# smoothieboard-5driver_0.net
KiCad netlist of a schematic drawn in Altium Designer
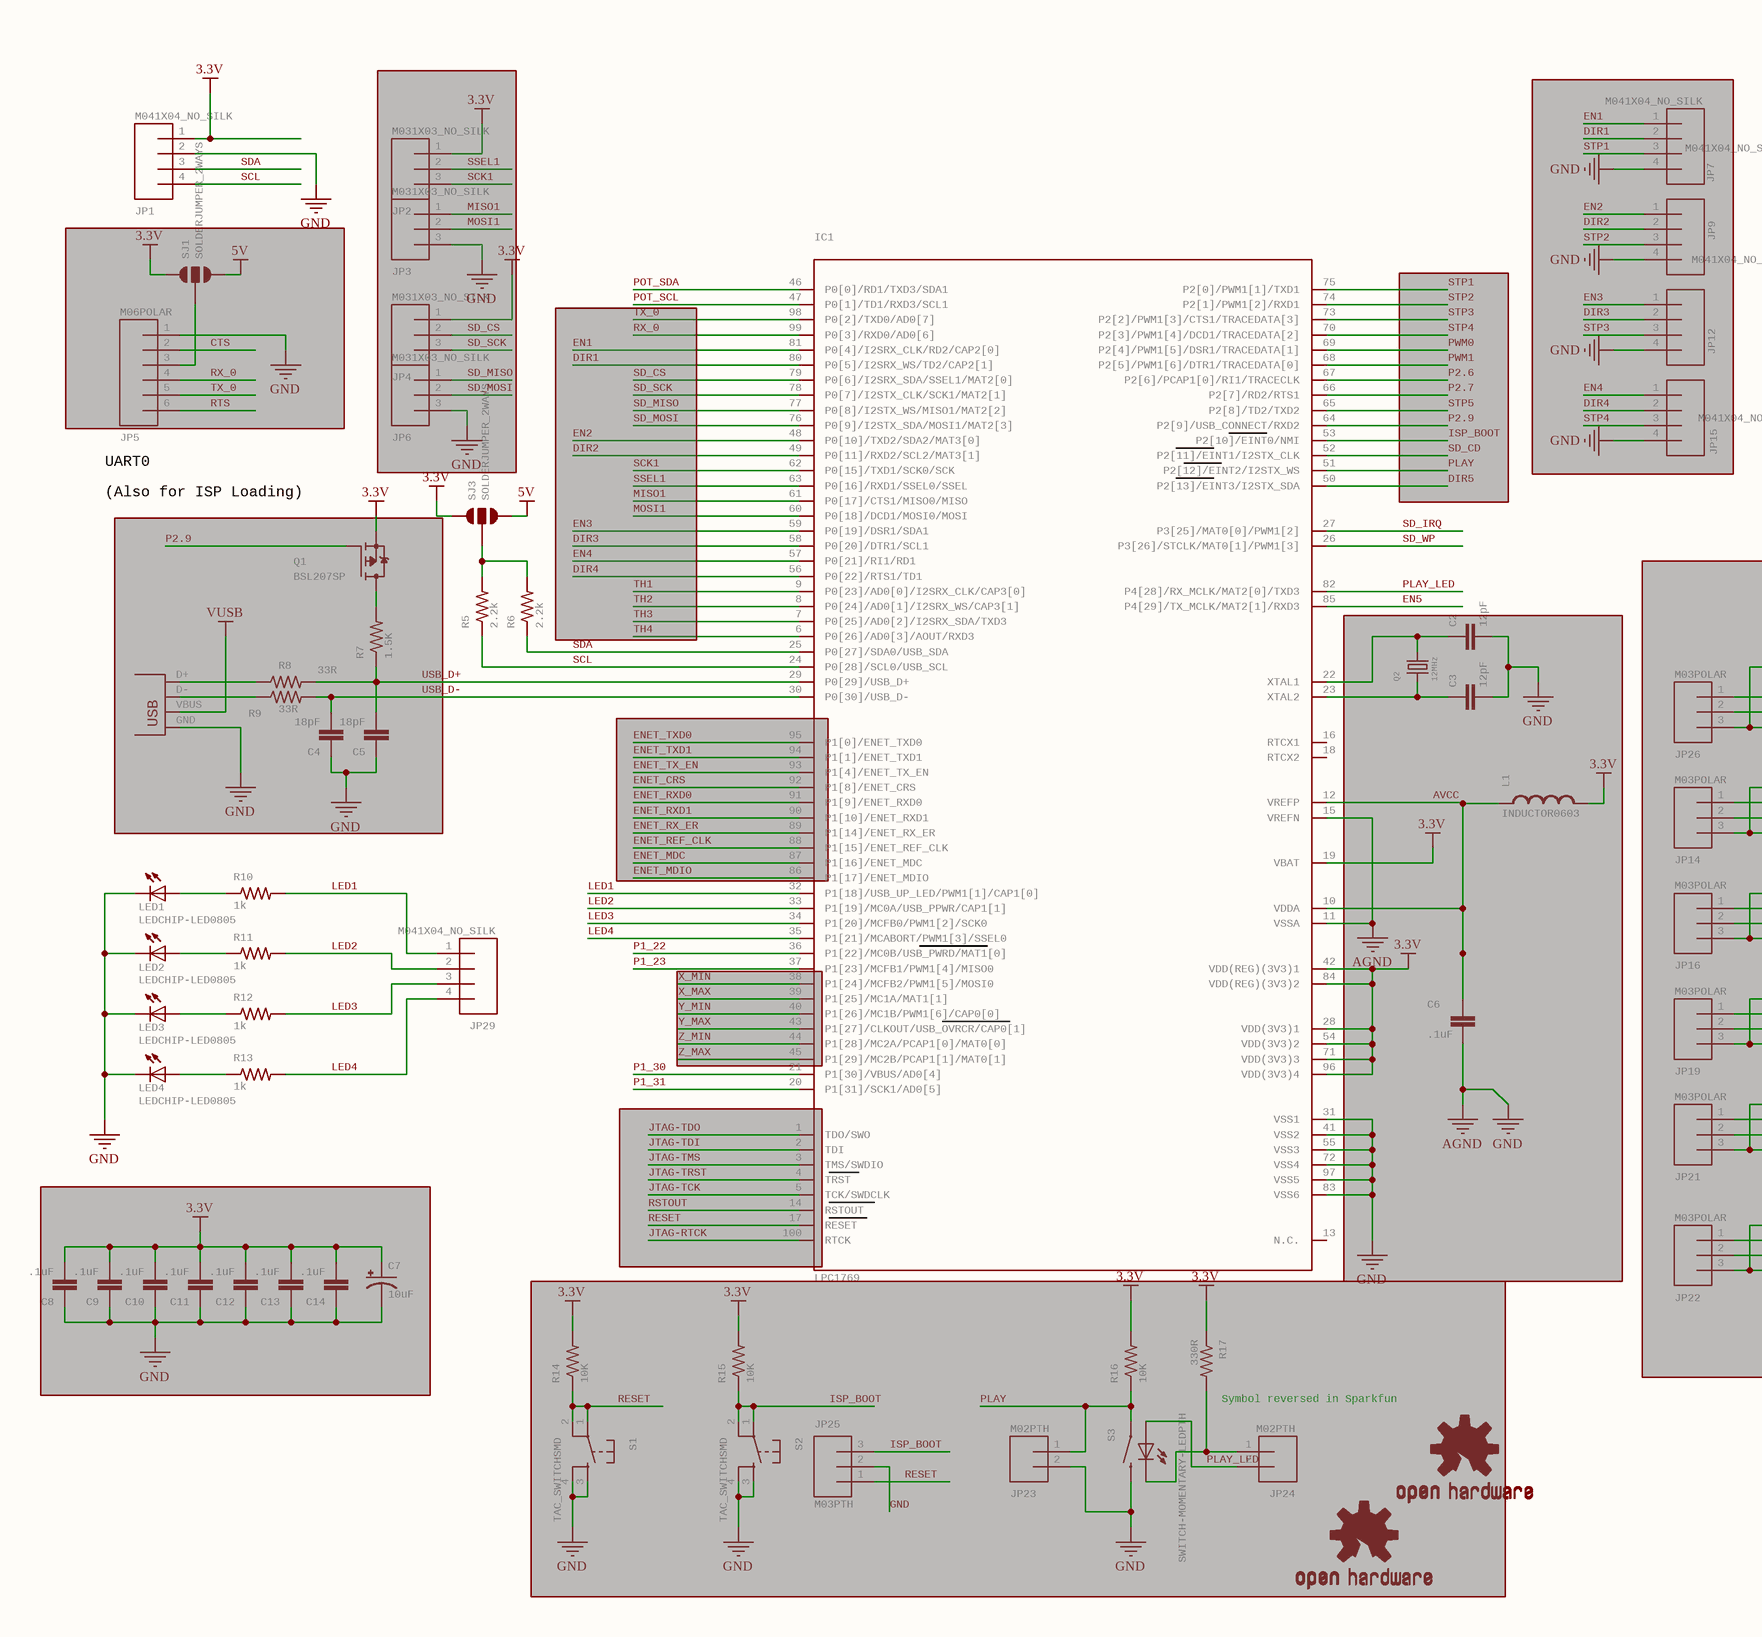
[diagram p0: smoothieboard-5driver_0.SchDoc, left]
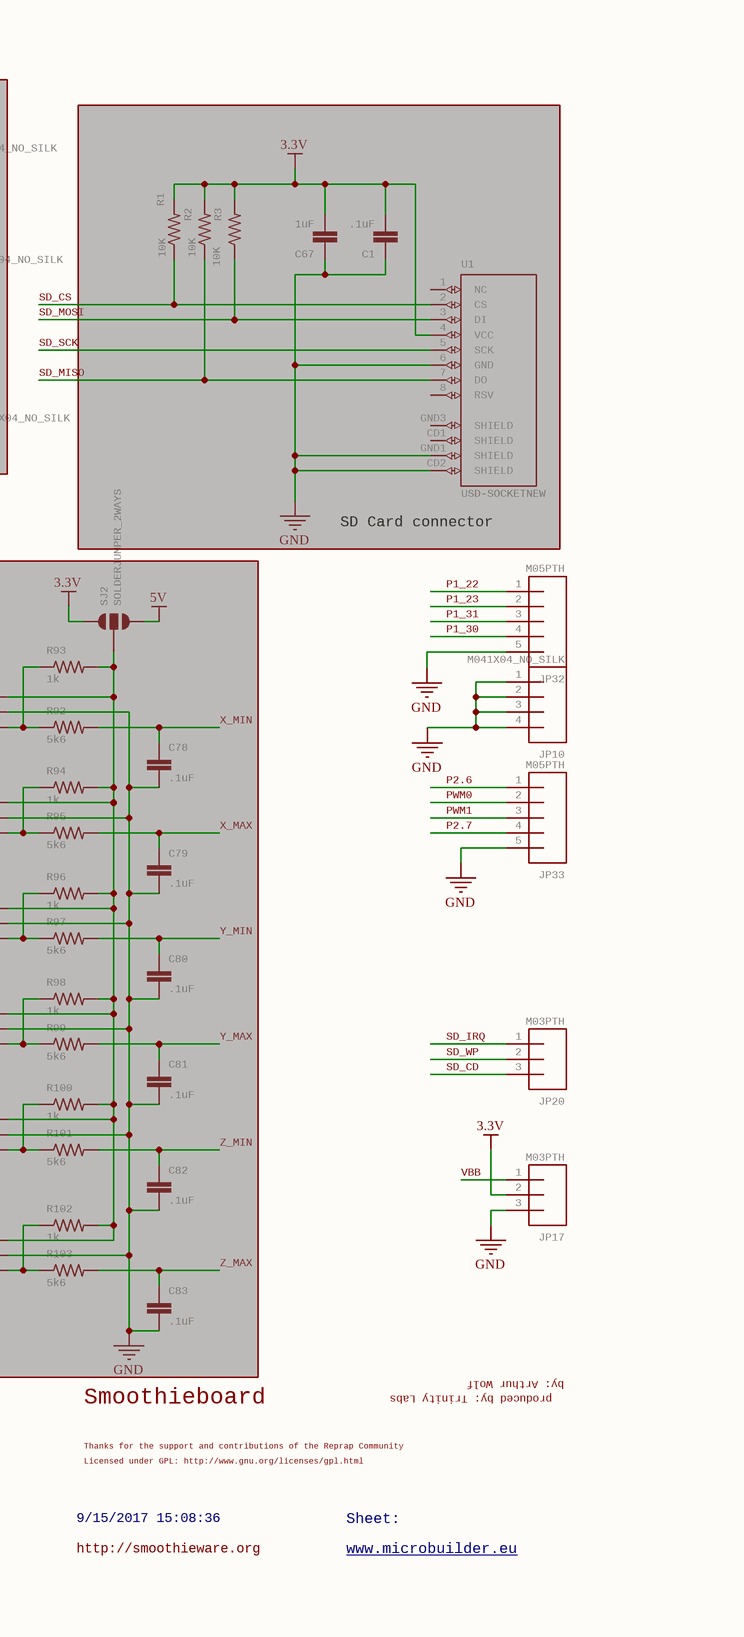
[diagram p1: smoothieboard-5driver_0.SchDoc, right]

(export (version "E")
  (design (tool "Eeschema 10.0.6"))
  (components
    (comp (ref "C1")
      (value ".1uF")
      (footprint "C0603")
      (description "CAPACITOR, European symbol")
      (libsource (lib "resistor") (part "C-EUC0603"))
    )
    (comp (ref "C2")
      (value "12pF")
      (footprint "C0603")
      (description "CAPACITOR, European symbol")
      (libsource (lib "") (part "C-EUC0603_2"))
    )
    (comp (ref "C3")
      (value "12pF")
      (footprint "C0603")
      (description "CAPACITOR, European symbol")
      (libsource (lib "") (part "C-EUC0603_2"))
    )
    (comp (ref "C4")
      (value "18pF")
      (footprint "C0603")
      (description "CAPACITOR, European symbol")
      (libsource (lib "rcl") (part "C-EUC0603"))
    )
    (comp (ref "C5")
      (value "18pF")
      (footprint "C0603")
      (description "CAPACITOR, European symbol")
      (libsource (lib "rcl") (part "C-EUC0603"))
    )
    (comp (ref "C6")
      (value ".1uF")
      (footprint "C0603")
      (description "CAPACITOR, European symbol")
      (libsource (lib "") (part "C-EUC0603_1"))
    )
    (comp (ref "C7") (value "10uF") (footprint "EIA3216") (libsource (lib "SparkFun") (part "CAP_POL1206")))
    (comp (ref "C8")
      (value ".1uF")
      (footprint "C0603")
      (description "CAPACITOR, European symbol")
      (libsource (lib "rcl") (part "C-EUC0603"))
    )
    (comp (ref "C9")
      (value ".1uF")
      (footprint "C0603")
      (description "CAPACITOR, European symbol")
      (libsource (lib "rcl") (part "C-EUC0603"))
    )
    (comp (ref "C10")
      (value ".1uF")
      (footprint "C0603")
      (description "CAPACITOR, European symbol")
      (libsource (lib "rcl") (part "C-EUC0603"))
    )
    (comp (ref "C11")
      (value ".1uF")
      (footprint "C0603")
      (description "CAPACITOR, European symbol")
      (libsource (lib "rcl") (part "C-EUC0603"))
    )
    (comp (ref "C12")
      (value ".1uF")
      (footprint "C0603")
      (description "CAPACITOR, European symbol")
      (libsource (lib "rcl") (part "C-EUC0603"))
    )
    (comp (ref "C13")
      (value ".1uF")
      (footprint "C0603")
      (description "CAPACITOR, European symbol")
      (libsource (lib "rcl") (part "C-EUC0603"))
    )
    (comp (ref "C14")
      (value ".1uF")
      (footprint "C0603")
      (description "CAPACITOR, European symbol")
      (libsource (lib "rcl") (part "C-EUC0603"))
    )
    (comp (ref "C67")
      (value "1uF")
      (footprint "C0805")
      (description "CAPACITOR, European symbol")
      (libsource (lib "resistor") (part "C-EUC0805"))
    )
    (comp (ref "C78")
      (value ".1uF")
      (footprint "C0603")
      (description "CAPACITOR, European symbol")
      (libsource (lib "") (part "C-EUC0603_1"))
    )
    (comp (ref "C79")
      (value ".1uF")
      (footprint "C0603")
      (description "CAPACITOR, European symbol")
      (libsource (lib "") (part "C-EUC0603_1"))
    )
    (comp (ref "C80")
      (value ".1uF")
      (footprint "C0603")
      (description "CAPACITOR, European symbol")
      (libsource (lib "") (part "C-EUC0603_1"))
    )
    (comp (ref "C81")
      (value ".1uF")
      (footprint "C0603")
      (description "CAPACITOR, European symbol")
      (libsource (lib "") (part "C-EUC0603_1"))
    )
    (comp (ref "C82")
      (value ".1uF")
      (footprint "C0603")
      (description "CAPACITOR, European symbol")
      (libsource (lib "") (part "C-EUC0603_1"))
    )
    (comp (ref "C83")
      (value ".1uF")
      (footprint "C0603")
      (description "CAPACITOR, European symbol")
      (libsource (lib "") (part "C-EUC0603_1"))
    )
    (comp (ref "IC1")
      (value "LPC1769")
      (footprint "LQFP100")
      (libsource (lib "microbuilder") (part "LPC1768"))
    )
    (comp (ref "JP1")
      (value "M041X04_NO_SILK")
      (footprint "1X04_NO_SILK")
      (libsource (lib "SparkFun") (part "M041X04_NO_SILK"))
    )
    (comp (ref "JP2")
      (value "M031X03_NO_SILK")
      (footprint "1X03_NO_SILK")
      (libsource (lib "SparkFun") (part "M031X03_NO_SILK"))
    )
    (comp (ref "JP3")
      (value "M031X03_NO_SILK")
      (footprint "1X03_NO_SILK")
      (libsource (lib "SparkFun") (part "M031X03_NO_SILK"))
    )
    (comp (ref "JP4")
      (value "M031X03_NO_SILK")
      (footprint "1X03_NO_SILK")
      (libsource (lib "SparkFun") (part "M031X03_NO_SILK"))
    )
    (comp (ref "JP5")
      (value "M06POLAR")
      (footprint "MOLEX-1X6")
      (libsource (lib "SparkFun") (part "M06POLAR"))
    )
    (comp (ref "JP6")
      (value "M031X03_NO_SILK")
      (footprint "1X03_NO_SILK")
      (libsource (lib "SparkFun") (part "M031X03_NO_SILK"))
    )
    (comp (ref "JP7")
      (value "M041X04_NO_SILK")
      (footprint "1X04_NO_SILK")
      (libsource (lib "SparkFun") (part "M041X04_NO_SILK"))
    )
    (comp (ref "JP9")
      (value "M041X04_NO_SILK")
      (footprint "1X04_NO_SILK")
      (libsource (lib "SparkFun") (part "M041X04_NO_SILK"))
    )
    (comp (ref "JP10")
      (value "M041X04_NO_SILK")
      (footprint "1X04_NO_SILK")
      (libsource (lib "SparkFun") (part "M041X04_NO_SILK"))
    )
    (comp (ref "JP12")
      (value "M041X04_NO_SILK")
      (footprint "1X04_NO_SILK")
      (libsource (lib "SparkFun") (part "M041X04_NO_SILK"))
    )
    (comp (ref "JP14")
      (value "M03POLAR")
      (footprint "MOLEX-1X3")
      (libsource (lib "SparkFun") (part "M03POLAR"))
    )
    (comp (ref "JP15")
      (value "M041X04_NO_SILK")
      (footprint "1X04_NO_SILK")
      (libsource (lib "SparkFun") (part "M041X04_NO_SILK"))
    )
    (comp (ref "JP16")
      (value "M03POLAR")
      (footprint "MOLEX-1X3")
      (libsource (lib "SparkFun") (part "M03POLAR"))
    )
    (comp (ref "JP17") (value "M03PTH") (footprint "1X03") (libsource (lib "SparkFun") (part "M03PTH")))
    (comp (ref "JP19")
      (value "M03POLAR")
      (footprint "MOLEX-1X3")
      (libsource (lib "SparkFun") (part "M03POLAR"))
    )
    (comp (ref "JP20") (value "M03PTH") (footprint "1X03") (libsource (lib "SparkFun") (part "M03PTH")))
    (comp (ref "JP21")
      (value "M03POLAR")
      (footprint "MOLEX-1X3")
      (libsource (lib "SparkFun") (part "M03POLAR"))
    )
    (comp (ref "JP22")
      (value "M03POLAR")
      (footprint "MOLEX-1X3")
      (libsource (lib "SparkFun") (part "M03POLAR"))
    )
    (comp (ref "JP23") (value "M02PTH") (footprint "1X02") (libsource (lib "SparkFun") (part "M02PTH")))
    (comp (ref "JP24") (value "M02PTH") (footprint "1X02") (libsource (lib "SparkFun") (part "M02PTH")))
    (comp (ref "JP25")
      (value "M03PTH")
      (footprint "1X03")
      (libsource (lib "SparkFun-Connectors") (part "M03PTH"))
    )
    (comp (ref "JP26")
      (value "M03POLAR")
      (footprint "MOLEX-1X3")
      (libsource (lib "SparkFun") (part "M03POLAR"))
    )
    (comp (ref "JP29")
      (value "M041X04_NO_SILK")
      (footprint "1X04_NO_SILK")
      (libsource (lib "SparkFun") (part "M041X04_NO_SILK"))
    )
    (comp (ref "JP32") (value "M05PTH") (footprint "1X05") (libsource (lib "SparkFun") (part "M05PTH")))
    (comp (ref "JP33") (value "M05PTH") (footprint "1X05") (libsource (lib "SparkFun") (part "M05PTH")))
    (comp (ref "L1")
      (value "INDUCTOR0603")
      (footprint "0603")
      (libsource (lib "SparkFun") (part "INDUCTOR0603"))
    )
    (comp (ref "LED1")
      (value "LEDCHIP-LED0805")
      (footprint "CHIP-LED0805")
      (libsource (lib "led") (part "LEDCHIP-LED0805"))
    )
    (comp (ref "LED2")
      (value "LEDCHIP-LED0805")
      (footprint "CHIP-LED0805")
      (libsource (lib "led") (part "LEDCHIP-LED0805"))
    )
    (comp (ref "LED3")
      (value "LEDCHIP-LED0805")
      (footprint "CHIP-LED0805")
      (libsource (lib "led") (part "LEDCHIP-LED0805"))
    )
    (comp (ref "LED4")
      (value "LEDCHIP-LED0805")
      (footprint "CHIP-LED0805")
      (libsource (lib "led") (part "LEDCHIP-LED0805"))
    )
    (comp (ref "Q1")
      (value "BSL207SP")
      (footprint "SC74_INFINEON")
      (libsource (lib "transistor-fet") (part "BSL207SP"))
    )
    (comp (ref "Q2")
      (value "12MHz")
      (footprint "CRYSTAL_3.2X2.5")
      (libsource (lib "microbuilder") (part "CRYSTALTHIN"))
    )
    (comp (ref "R1")
      (value "10K")
      (footprint "R0603")
      (description "RESISTOR, American symbol")
      (libsource (lib "resistor") (part "R-US_R0603"))
    )
    (comp (ref "R2")
      (value "10K")
      (footprint "R0603")
      (description "RESISTOR, American symbol")
      (libsource (lib "resistor") (part "R-US_R0603"))
    )
    (comp (ref "R3")
      (value "10K")
      (footprint "R0603")
      (description "RESISTOR, American symbol")
      (libsource (lib "resistor") (part "R-US_R0603"))
    )
    (comp (ref "R5")
      (value "2.2k")
      (footprint "R0603")
      (description "RESISTOR, American symbol")
      (libsource (lib "resistor") (part "R-US_R0603"))
    )
    (comp (ref "R6")
      (value "2.2k")
      (footprint "R0603")
      (description "RESISTOR, American symbol")
      (libsource (lib "resistor") (part "R-US_R0603"))
    )
    (comp (ref "R7")
      (value "1.5K")
      (footprint "R0603")
      (description "RESISTOR, American symbol")
      (libsource (lib "resistor") (part "R-US_R0603"))
    )
    (comp (ref "R8")
      (value "33R")
      (footprint "R0603")
      (description "RESISTOR, American symbol")
      (libsource (lib "resistor") (part "R-US_R0603"))
    )
    (comp (ref "R9")
      (value "33R")
      (footprint "R0603")
      (description "RESISTOR, American symbol")
      (libsource (lib "resistor") (part "R-US_R0603"))
    )
    (comp (ref "R10")
      (value "1k")
      (footprint "R0603")
      (description "RESISTOR, American symbol")
      (libsource (lib "resistor") (part "R-US_R0603"))
    )
    (comp (ref "R11")
      (value "1k")
      (footprint "R0603")
      (description "RESISTOR, American symbol")
      (libsource (lib "resistor") (part "R-US_R0603"))
    )
    (comp (ref "R12")
      (value "1k")
      (footprint "R0603")
      (description "RESISTOR, American symbol")
      (libsource (lib "resistor") (part "R-US_R0603"))
    )
    (comp (ref "R13")
      (value "1k")
      (footprint "R0603")
      (description "RESISTOR, American symbol")
      (libsource (lib "resistor") (part "R-US_R0603"))
    )
    (comp (ref "R14")
      (value "10K")
      (footprint "R0603")
      (description "RESISTOR, American symbol")
      (libsource (lib "resistor") (part "R-US_R0603"))
    )
    (comp (ref "R15")
      (value "10K")
      (footprint "R0603")
      (description "RESISTOR, American symbol")
      (libsource (lib "resistor") (part "R-US_R0603"))
    )
    (comp (ref "R16")
      (value "10K")
      (footprint "R0603")
      (description "RESISTOR, American symbol")
      (libsource (lib "resistor") (part "R-US_R0603"))
    )
    (comp (ref "R17")
      (value "330R")
      (footprint "R0603")
      (description "RESISTOR, American symbol")
      (libsource (lib "resistor") (part "R-US_R0603"))
    )
    (comp (ref "R92")
      (value "5k6")
      (footprint "R0603")
      (description "RESISTOR, American symbol")
      (libsource (lib "resistor") (part "R-US_R0603"))
    )
    (comp (ref "R93")
      (value "1k")
      (footprint "R0603")
      (description "RESISTOR, American symbol")
      (libsource (lib "resistor") (part "R-US_R0603"))
    )
    (comp (ref "R94")
      (value "1k")
      (footprint "R0603")
      (description "RESISTOR, American symbol")
      (libsource (lib "resistor") (part "R-US_R0603"))
    )
    (comp (ref "R95")
      (value "5k6")
      (footprint "R0603")
      (description "RESISTOR, American symbol")
      (libsource (lib "resistor") (part "R-US_R0603"))
    )
    (comp (ref "R96")
      (value "1k")
      (footprint "R0603")
      (description "RESISTOR, American symbol")
      (libsource (lib "resistor") (part "R-US_R0603"))
    )
    (comp (ref "R97")
      (value "5k6")
      (footprint "R0603")
      (description "RESISTOR, American symbol")
      (libsource (lib "resistor") (part "R-US_R0603"))
    )
    (comp (ref "R98")
      (value "1k")
      (footprint "R0603")
      (description "RESISTOR, American symbol")
      (libsource (lib "resistor") (part "R-US_R0603"))
    )
    (comp (ref "R99")
      (value "5k6")
      (footprint "R0603")
      (description "RESISTOR, American symbol")
      (libsource (lib "resistor") (part "R-US_R0603"))
    )
    (comp (ref "R100")
      (value "1k")
      (footprint "R0603")
      (description "RESISTOR, American symbol")
      (libsource (lib "resistor") (part "R-US_R0603"))
    )
    (comp (ref "R101")
      (value "5k6")
      (footprint "R0603")
      (description "RESISTOR, American symbol")
      (libsource (lib "resistor") (part "R-US_R0603"))
    )
    (comp (ref "R102")
      (value "1k")
      (footprint "R0603")
      (description "RESISTOR, American symbol")
      (libsource (lib "resistor") (part "R-US_R0603"))
    )
    (comp (ref "R103")
      (value "5k6")
      (footprint "R0603")
      (description "RESISTOR, American symbol")
      (libsource (lib "resistor") (part "R-US_R0603"))
    )
    (comp (ref "S1")
      (value "TAC_SWITCHSMD")
      (footprint "TACTILE_SWITCH_SMD")
      (libsource (lib "SparkFun") (part "TAC_SWITCHSMD"))
    )
    (comp (ref "S2")
      (value "TAC_SWITCHSMD")
      (footprint "TACTILE_SWITCH_SMD")
      (libsource (lib "SparkFun") (part "TAC_SWITCHSMD"))
    )
    (comp (ref "S3")
      (value "SWITCH-MOMENTARY-LEDPTH")
      (footprint "TACTILE-PTH-LED-12MM")
      (libsource (lib "Local Library") (part "SWITCH-MOMENTARY-LEDPTH"))
    )
    (comp (ref "SJ1")
      (value "SOLDERJUMPER_2WAYS")
      (footprint "SJ_3")
      (description "Solder Jumper2 way solder jumper")
      (libsource (lib "SparkFun") (part "SOLDERJUMPER_2WAYS"))
    )
    (comp (ref "SJ2")
      (value "SOLDERJUMPER_2WAYS")
      (footprint "SJ_3")
      (description "Solder Jumper2 way solder jumper")
      (libsource (lib "SparkFun") (part "SOLDERJUMPER_2WAYS"))
    )
    (comp (ref "SJ3")
      (value "SOLDERJUMPER_2WAYS")
      (footprint "SJ_3")
      (description "Solder Jumper2 way solder jumper")
      (libsource (lib "SparkFun") (part "SOLDERJUMPER_2WAYS"))
    )
    (comp (ref "U$8")
      (value "OSHW-LOGOH")
      (footprint "OSHW-LOGO-HUGE")
      (fields (field (name "LIBRARYNAME") "logxen"))
      (libsource (lib "logxen") (part "OSHW-LOGOH"))
    )
    (comp (ref "U$9")
      (value "OSHW-LOGOH")
      (footprint "OSHW-LOGO-HUGE")
      (fields (field (name "LIBRARYNAME") "logxen"))
      (libsource (lib "logxen") (part "OSHW-LOGOH"))
    )
    (comp (ref "U1")
      (value "USD-SOCKETNEW")
      (footprint "MICRO-SD-SOCKET-PP")
      (libsource (lib "SparkFun") (part "USD-SOCKETNEW"))
    )
    (comp (ref "X14")
      (value "USBPTH")
      (footprint "USB-B-PTH")
      (fields (field (name "USB") "USB"))
      (libsource (lib "SparkFun") (part "USBPTH"))
    )
  )
  (nets
    (net (code "1") (name "/AVCC") (class "Default")
      (node (ref "C6") (pin "1") (pinfunction "1_1") (pintype "passive"))
      (node (ref "IC1") (pin "10") (pinfunction "VDDA_10") (pintype "bidirectional"))
      (node (ref "IC1") (pin "12") (pinfunction "VREFP_12") (pintype "bidirectional"))
      (node (ref "L1") (pin "1") (pinfunction "1_1") (pintype "passive"))
    )
    (net (code "2") (name "/CTS") (class "Default")
      (node (ref "JP5") (pin "2") (pinfunction "2_2") (pintype "passive"))
    )
    (net (code "3") (name "/DIR1") (class "Default")
      (node (ref "IC1") (pin "80") (pinfunction "P0[5]/I2SRX_WS/TD2/CAP2[1]_80") (pintype "bidirectional"))
      (node (ref "JP7") (pin "2") (pinfunction "2_2") (pintype "passive"))
    )
    (net (code "4") (name "/DIR2") (class "Default")
      (node (ref "IC1") (pin "49") (pinfunction "P0[11]/RXD2/SCL2/MAT3[1]_49") (pintype "bidirectional"))
      (node (ref "JP9") (pin "2") (pinfunction "2_2") (pintype "passive"))
    )
    (net (code "5") (name "/DIR3") (class "Default")
      (node (ref "IC1") (pin "58") (pinfunction "P0[20]/DTR1/SCL1_58") (pintype "bidirectional"))
      (node (ref "JP12") (pin "2") (pinfunction "2_2") (pintype "passive"))
    )
    (net (code "6") (name "/DIR4") (class "Default")
      (node (ref "IC1") (pin "56") (pinfunction "P0[22]/RTS1/TD1_56") (pintype "bidirectional"))
      (node (ref "JP15") (pin "2") (pinfunction "2_2") (pintype "passive"))
    )
    (net (code "7") (name "/DIR5") (class "Default")
      (node (ref "IC1") (pin "50") (pinfunction "P2[13]/EINT3/I2STX_SDA_50") (pintype "bidirectional"))
    )
    (net (code "8") (name "/EN1") (class "Default")
      (node (ref "IC1") (pin "81") (pinfunction "P0[4]/I2SRX_CLK/RD2/CAP2[0]_81") (pintype "bidirectional"))
      (node (ref "JP7") (pin "1") (pinfunction "1_1") (pintype "passive"))
    )
    (net (code "9") (name "/EN2") (class "Default")
      (node (ref "IC1") (pin "48") (pinfunction "P0[10]/TXD2/SDA2/MAT3[0]_48") (pintype "bidirectional"))
      (node (ref "JP9") (pin "1") (pinfunction "1_1") (pintype "passive"))
    )
    (net (code "10") (name "/EN3") (class "Default")
      (node (ref "IC1") (pin "59") (pinfunction "P0[19]/DSR1/SDA1_59") (pintype "bidirectional"))
      (node (ref "JP12") (pin "1") (pinfunction "1_1") (pintype "passive"))
    )
    (net (code "11") (name "/EN4") (class "Default")
      (node (ref "IC1") (pin "57") (pinfunction "P0[21]/RI1/RD1_57") (pintype "bidirectional"))
      (node (ref "JP15") (pin "1") (pinfunction "1_1") (pintype "passive"))
    )
    (net (code "12") (name "/EN5") (class "Default")
      (node (ref "IC1") (pin "85") (pinfunction "P4[29]/TX_MCLK/MAT2[1]/RXD3_85") (pintype "bidirectional"))
    )
    (net (code "13") (name "/ENET_CRS") (class "Default")
      (node (ref "IC1") (pin "92") (pinfunction "P1[8]/ENET_CRS_92") (pintype "bidirectional"))
    )
    (net (code "14") (name "/ENET_MDC") (class "Default")
      (node (ref "IC1") (pin "87") (pinfunction "P1[16]/ENET_MDC_87") (pintype "bidirectional"))
    )
    (net (code "15") (name "/ENET_MDIO") (class "Default")
      (node (ref "IC1") (pin "86") (pinfunction "P1[17]/ENET_MDIO_86") (pintype "bidirectional"))
    )
    (net (code "16") (name "/ENET_REF_CLK") (class "Default")
      (node (ref "IC1") (pin "88") (pinfunction "P1[15]/ENET_REF_CLK_88") (pintype "bidirectional"))
    )
    (net (code "17") (name "/ENET_RXD0") (class "Default")
      (node (ref "IC1") (pin "91") (pinfunction "P1[9]/ENET_RXD0_91") (pintype "bidirectional"))
    )
    (net (code "18") (name "/ENET_RXD1") (class "Default")
      (node (ref "IC1") (pin "90") (pinfunction "P1[10]/ENET_RXD1_90") (pintype "bidirectional"))
    )
    (net (code "19") (name "/ENET_RX_ER") (class "Default")
      (node (ref "IC1") (pin "89") (pinfunction "P1[14]/ENET_RX_ER_89") (pintype "bidirectional"))
    )
    (net (code "20") (name "/ENET_TXD0") (class "Default")
      (node (ref "IC1") (pin "95") (pinfunction "P1[0]/ENET_TXD0_95") (pintype "bidirectional"))
    )
    (net (code "21") (name "/ENET_TXD1") (class "Default")
      (node (ref "IC1") (pin "94") (pinfunction "P1[1]/ENET_TXD1_94") (pintype "bidirectional"))
    )
    (net (code "22") (name "/ENET_TX_EN") (class "Default")
      (node (ref "IC1") (pin "93") (pinfunction "P1[4]/ENET_TX_EN_93") (pintype "bidirectional"))
    )
    (net (code "23") (name "/ISP_BOOT") (class "Default")
      (node (ref "IC1") (pin "53") (pinfunction "P2[10]/EINT0/NMI_53") (pintype "bidirectional"))
      (node (ref "JP25") (pin "3") (pinfunction "3_3") (pintype "passive"))
      (node (ref "R15") (pin "1") (pinfunction "1_1") (pintype "passive"))
      (node (ref "S2") (pin "1") (pinfunction "1_1") (pintype "passive"))
      (node (ref "S2") (pin "2") (pinfunction "2_2") (pintype "passive"))
    )
    (net (code "24") (name "/JTAG-RTCK") (class "Default")
      (node (ref "IC1") (pin "100") (pinfunction "RTCK_100") (pintype "bidirectional"))
    )
    (net (code "25") (name "/JTAG-TCK") (class "Default")
      (node (ref "IC1") (pin "5") (pinfunction "TCK/SWDCLK_5") (pintype "bidirectional"))
    )
    (net (code "26") (name "/JTAG-TDI") (class "Default")
      (node (ref "IC1") (pin "2") (pinfunction "TDI_2") (pintype "bidirectional"))
    )
    (net (code "27") (name "/JTAG-TDO") (class "Default")
      (node (ref "IC1") (pin "1") (pinfunction "TDO/SWO_1") (pintype "bidirectional"))
    )
    (net (code "28") (name "/JTAG-TMS") (class "Default")
      (node (ref "IC1") (pin "3") (pinfunction "TMS/SWDIO_3") (pintype "bidirectional"))
    )
    (net (code "29") (name "/JTAG-TRST") (class "Default")
      (node (ref "IC1") (pin "4") (pinfunction "TRST_4") (pintype "bidirectional"))
    )
    (net (code "30") (name "/LED1") (class "Default")
      (node (ref "IC1") (pin "32") (pinfunction "P1[18]/USB_UP_LED/PWM1[1]/CAP1[0]_32") (pintype "bidirectional"))
      (node (ref "JP29") (pin "1") (pinfunction "1_1") (pintype "passive"))
      (node (ref "R10") (pin "2") (pinfunction "2_2") (pintype "passive"))
    )
    (net (code "31") (name "/LED2") (class "Default")
      (node (ref "IC1") (pin "33") (pinfunction "P1[19]/MC0A/USB_PPWR/CAP1[1]_33") (pintype "bidirectional"))
      (node (ref "JP29") (pin "2") (pinfunction "2_2") (pintype "passive"))
      (node (ref "R11") (pin "2") (pinfunction "2_2") (pintype "passive"))
    )
    (net (code "32") (name "/LED3") (class "Default")
      (node (ref "IC1") (pin "34") (pinfunction "P1[20]/MCFB0/PWM1[2]/SCK0_34") (pintype "bidirectional"))
      (node (ref "JP29") (pin "3") (pinfunction "3_3") (pintype "passive"))
      (node (ref "R12") (pin "2") (pinfunction "2_2") (pintype "passive"))
    )
    (net (code "33") (name "/LED4") (class "Default")
      (node (ref "IC1") (pin "35") (pinfunction "P1[21]/MCABORT/PWM1[3]/SSEL0_35") (pintype "bidirectional"))
      (node (ref "JP29") (pin "4") (pinfunction "4_4") (pintype "passive"))
      (node (ref "R13") (pin "2") (pinfunction "2_2") (pintype "passive"))
    )
    (net (code "34") (name "/MISO1") (class "Default")
      (node (ref "IC1") (pin "61") (pinfunction "P0[17]/CTS1/MISO0/MISO_61") (pintype "bidirectional"))
      (node (ref "JP3") (pin "1") (pinfunction "1_1") (pintype "passive"))
    )
    (net (code "35") (name "/MOSI1") (class "Default")
      (node (ref "IC1") (pin "60") (pinfunction "P0[18]/DCD1/MOSI0/MOSI_60") (pintype "bidirectional"))
      (node (ref "JP3") (pin "2") (pinfunction "2_2") (pintype "passive"))
    )
    (net (code "36") (name "/P1_22") (class "Default")
      (node (ref "IC1") (pin "36") (pinfunction "P1[22]/MC0B/USB_PWRD/MAT1[0]_36") (pintype "bidirectional"))
      (node (ref "JP32") (pin "1") (pinfunction "1_1") (pintype "passive"))
    )
    (net (code "37") (name "/P1_23") (class "Default")
      (node (ref "IC1") (pin "37") (pinfunction "P1[23]/MCFB1/PWM1[4]/MISO0_37") (pintype "bidirectional"))
      (node (ref "JP32") (pin "2") (pinfunction "2_2") (pintype "passive"))
    )
    (net (code "38") (name "/P1_30") (class "Default")
      (node (ref "IC1") (pin "21") (pinfunction "P1[30]/VBUS/AD0[4]_21") (pintype "bidirectional"))
      (node (ref "JP32") (pin "4") (pinfunction "4_4") (pintype "passive"))
    )
    (net (code "39") (name "/P1_31") (class "Default")
      (node (ref "IC1") (pin "20") (pinfunction "P1[31]/SCK1/AD0[5]_20") (pintype "bidirectional"))
      (node (ref "JP32") (pin "3") (pinfunction "3_3") (pintype "passive"))
    )
    (net (code "40") (name "/P2.6") (class "Default")
      (node (ref "IC1") (pin "67") (pinfunction "P2[6]/PCAP1[0]/RI1/TRACECLK_67") (pintype "bidirectional"))
      (node (ref "JP33") (pin "1") (pinfunction "1_1") (pintype "passive"))
    )
    (net (code "41") (name "/P2.7") (class "Default")
      (node (ref "IC1") (pin "66") (pinfunction "P2[7]/RD2/RTS1_66") (pintype "bidirectional"))
      (node (ref "JP33") (pin "4") (pinfunction "4_4") (pintype "passive"))
    )
    (net (code "42") (name "/P2.9") (class "Default")
      (node (ref "IC1") (pin "64") (pinfunction "P2[9]/USB_CONNECT/RXD2_64") (pintype "bidirectional"))
      (node (ref "Q1") (pin "3") (pinfunction "G_3") (pintype "passive"))
    )
    (net (code "43") (name "/PLAY") (class "Default")
      (node (ref "IC1") (pin "51") (pinfunction "P2[12]/EINT2/I2STX_WS_51") (pintype "bidirectional"))
      (node (ref "JP23") (pin "1") (pinfunction "1_1") (pintype "passive"))
      (node (ref "R16") (pin "1") (pinfunction "1_1") (pintype "passive"))
      (node (ref "S3") (pin "4") (pinfunction "1_4") (pintype "passive"))
    )
    (net (code "44") (name "/PLAY_LED") (class "Default")
      (node (ref "IC1") (pin "82") (pinfunction "P4[28]/RX_MCLK/MAT2[0]/TXD3_82") (pintype "bidirectional"))
      (node (ref "JP24") (pin "2") (pinfunction "2_2") (pintype "passive"))
      (node (ref "S3") (pin "A") (pinfunction "A_A") (pintype "passive"))
    )
    (net (code "45") (name "/POT_SCL") (class "Default")
      (node (ref "IC1") (pin "47") (pinfunction "P0[1]/TD1/RXD3/SCL1_47") (pintype "bidirectional"))
    )
    (net (code "46") (name "/POT_SDA") (class "Default")
      (node (ref "IC1") (pin "46") (pinfunction "P0[0]/RD1/TXD3/SDA1_46") (pintype "bidirectional"))
    )
    (net (code "47") (name "/PWM0") (class "Default")
      (node (ref "IC1") (pin "69") (pinfunction "P2[4]/PWM1[5]/DSR1/TRACEDATA[1]_69") (pintype "bidirectional"))
      (node (ref "JP33") (pin "2") (pinfunction "2_2") (pintype "passive"))
    )
    (net (code "48") (name "/PWM1") (class "Default")
      (node (ref "IC1") (pin "68") (pinfunction "P2[5]/PWM1[6]/DTR1/TRACEDATA[0]_68") (pintype "bidirectional"))
      (node (ref "JP33") (pin "3") (pinfunction "3_3") (pintype "passive"))
    )
    (net (code "49") (name "/RESET") (class "Default")
      (node (ref "IC1") (pin "17") (pinfunction "RESET_17") (pintype "bidirectional"))
      (node (ref "JP25") (pin "1") (pinfunction "1_1") (pintype "passive"))
      (node (ref "R14") (pin "1") (pinfunction "1_1") (pintype "passive"))
      (node (ref "S1") (pin "1") (pinfunction "1_1") (pintype "passive"))
      (node (ref "S1") (pin "2") (pinfunction "2_2") (pintype "passive"))
    )
    (net (code "50") (name "/RSTOUT") (class "Default")
      (node (ref "IC1") (pin "14") (pinfunction "RSTOUT_14") (pintype "bidirectional"))
    )
    (net (code "51") (name "/RTS") (class "Default")
      (node (ref "JP5") (pin "6") (pinfunction "6_6") (pintype "passive"))
    )
    (net (code "52") (name "/RX_0") (class "Default")
      (node (ref "IC1") (pin "99") (pinfunction "P0[3]/RXD0/AD0[6]_99") (pintype "bidirectional"))
      (node (ref "JP5") (pin "4") (pinfunction "4_4") (pintype "passive"))
    )
    (net (code "53") (name "/SCK1") (class "Default")
      (node (ref "IC1") (pin "62") (pinfunction "P0[15]/TXD1/SCK0/SCK_62") (pintype "bidirectional"))
      (node (ref "JP2") (pin "3") (pinfunction "3_3") (pintype "passive"))
    )
    (net (code "54") (name "/SCL") (class "Default")
      (node (ref "IC1") (pin "24") (pinfunction "P0[28]/SCL0/USB_SCL_24") (pintype "bidirectional"))
      (node (ref "JP1") (pin "4") (pinfunction "4_4") (pintype "passive"))
      (node (ref "R5") (pin "1") (pinfunction "1_1") (pintype "passive"))
    )
    (net (code "55") (name "/SDA") (class "Default")
      (node (ref "IC1") (pin "25") (pinfunction "P0[27]/SDA0/USB_SDA_25") (pintype "bidirectional"))
      (node (ref "JP1") (pin "3") (pinfunction "3_3") (pintype "passive"))
      (node (ref "R6") (pin "1") (pinfunction "1_1") (pintype "passive"))
    )
    (net (code "56") (name "/SD_CD") (class "Default")
      (node (ref "IC1") (pin "52") (pinfunction "P2[11]/EINT1/I2STX_CLK_52") (pintype "bidirectional"))
      (node (ref "JP20") (pin "3") (pinfunction "3_3") (pintype "passive"))
    )
    (net (code "57") (name "/SD_CS") (class "Default")
      (node (ref "IC1") (pin "79") (pinfunction "P0[6]/I2SRX_SDA/SSEL1/MAT2[0]_79") (pintype "bidirectional"))
      (node (ref "JP4") (pin "2") (pinfunction "2_2") (pintype "passive"))
      (node (ref "R1") (pin "1") (pinfunction "1_1") (pintype "passive"))
      (node (ref "U1") (pin "2") (pinfunction "CS_2") (pintype "bidirectional"))
    )
    (net (code "58") (name "/SD_IRQ") (class "Default")
      (node (ref "IC1") (pin "27") (pinfunction "P3[25]/MAT0[0]/PWM1[2]_27") (pintype "bidirectional"))
      (node (ref "JP20") (pin "1") (pinfunction "1_1") (pintype "passive"))
    )
    (net (code "59") (name "/SD_MISO") (class "Default")
      (node (ref "IC1") (pin "77") (pinfunction "P0[8]/I2STX_WS/MISO1/MAT2[2]_77") (pintype "bidirectional"))
      (node (ref "JP6") (pin "1") (pinfunction "1_1") (pintype "passive"))
      (node (ref "R2") (pin "1") (pinfunction "1_1") (pintype "passive"))
      (node (ref "U1") (pin "7") (pinfunction "DO_7") (pintype "bidirectional"))
    )
    (net (code "60") (name "/SD_MOSI") (class "Default")
      (node (ref "IC1") (pin "76") (pinfunction "P0[9]/I2STX_SDA/MOSI1/MAT2[3]_76") (pintype "bidirectional"))
      (node (ref "JP6") (pin "2") (pinfunction "2_2") (pintype "passive"))
      (node (ref "R3") (pin "1") (pinfunction "1_1") (pintype "passive"))
      (node (ref "U1") (pin "3") (pinfunction "DI_3") (pintype "bidirectional"))
    )
    (net (code "61") (name "/SD_SCK") (class "Default")
      (node (ref "IC1") (pin "78") (pinfunction "P0[7]/I2STX_CLK/SCK1/MAT2[1]_78") (pintype "bidirectional"))
      (node (ref "JP4") (pin "3") (pinfunction "3_3") (pintype "passive"))
      (node (ref "U1") (pin "5") (pinfunction "SCK_5") (pintype "bidirectional"))
    )
    (net (code "62") (name "/SD_WP") (class "Default")
      (node (ref "IC1") (pin "26") (pinfunction "P3[26]/STCLK/MAT0[1]/PWM1[3]_26") (pintype "bidirectional"))
      (node (ref "JP20") (pin "2") (pinfunction "2_2") (pintype "passive"))
    )
    (net (code "63") (name "/SSEL1") (class "Default")
      (node (ref "IC1") (pin "63") (pinfunction "P0[16]/RXD1/SSEL0/SSEL_63") (pintype "bidirectional"))
      (node (ref "JP2") (pin "2") (pinfunction "2_2") (pintype "passive"))
    )
    (net (code "64") (name "/STP1") (class "Default")
      (node (ref "IC1") (pin "75") (pinfunction "P2[0]/PWM1[1]/TXD1_75") (pintype "bidirectional"))
      (node (ref "JP7") (pin "3") (pinfunction "3_3") (pintype "passive"))
    )
    (net (code "65") (name "/STP2") (class "Default")
      (node (ref "IC1") (pin "74") (pinfunction "P2[1]/PWM1[2]/RXD1_74") (pintype "bidirectional"))
      (node (ref "JP9") (pin "3") (pinfunction "3_3") (pintype "passive"))
    )
    (net (code "66") (name "/STP3") (class "Default")
      (node (ref "IC1") (pin "73") (pinfunction "P2[2]/PWM1[3]/CTS1/TRACEDATA[3]_73") (pintype "bidirectional"))
      (node (ref "JP12") (pin "3") (pinfunction "3_3") (pintype "passive"))
    )
    (net (code "67") (name "/STP4") (class "Default")
      (node (ref "IC1") (pin "70") (pinfunction "P2[3]/PWM1[4]/DCD1/TRACEDATA[2]_70") (pintype "bidirectional"))
      (node (ref "JP15") (pin "3") (pinfunction "3_3") (pintype "passive"))
    )
    (net (code "68") (name "/STP5") (class "Default")
      (node (ref "IC1") (pin "65") (pinfunction "P2[8]/TD2/TXD2_65") (pintype "bidirectional"))
    )
    (net (code "69") (name "/TH1") (class "Default")
      (node (ref "IC1") (pin "9") (pinfunction "P0[23]/AD0[0]/I2SRX_CLK/CAP3[0]_9") (pintype "bidirectional"))
    )
    (net (code "70") (name "/TH2") (class "Default")
      (node (ref "IC1") (pin "8") (pinfunction "P0[24]/AD0[1]/I2SRX_WS/CAP3[1]_8") (pintype "bidirectional"))
    )
    (net (code "71") (name "/TH3") (class "Default")
      (node (ref "IC1") (pin "7") (pinfunction "P0[25]/AD0[2]/I2SRX_SDA/TXD3_7") (pintype "bidirectional"))
    )
    (net (code "72") (name "/TH4") (class "Default")
      (node (ref "IC1") (pin "6") (pinfunction "P0[26]/AD0[3]/AOUT/RXD3_6") (pintype "bidirectional"))
    )
    (net (code "73") (name "/TX_0") (class "Default")
      (node (ref "IC1") (pin "98") (pinfunction "P0[2]/TXD0/AD0[7]_98") (pintype "bidirectional"))
      (node (ref "JP5") (pin "5") (pinfunction "5_5") (pintype "passive"))
    )
    (net (code "74") (name "/USB_D+") (class "Default")
      (node (ref "C5") (pin "2") (pinfunction "2_2") (pintype "passive"))
      (node (ref "IC1") (pin "29") (pinfunction "P0[29]/USB_D+_29") (pintype "bidirectional"))
      (node (ref "R7") (pin "1") (pinfunction "1_1") (pintype "passive"))
      (node (ref "R8") (pin "2") (pinfunction "2_2") (pintype "passive"))
    )
    (net (code "75") (name "/USB_D-") (class "Default")
      (node (ref "C4") (pin "2") (pinfunction "2_2") (pintype "passive"))
      (node (ref "IC1") (pin "30") (pinfunction "P0[30]/USB_D-_30") (pintype "bidirectional"))
      (node (ref "R9") (pin "2") (pinfunction "2_2") (pintype "passive"))
    )
    (net (code "76") (name "/VBB") (class "Default")
      (node (ref "JP17") (pin "1") (pinfunction "1_1") (pintype "passive"))
    )
    (net (code "77") (name "/X_MAX") (class "Default")
      (node (ref "C79") (pin "1") (pinfunction "1_1") (pintype "passive"))
      (node (ref "IC1") (pin "39") (pinfunction "P1[25]/MC1A/MAT1[1]_39") (pintype "bidirectional"))
      (node (ref "R95") (pin "2") (pinfunction "2_2") (pintype "passive"))
    )
    (net (code "78") (name "/X_MIN") (class "Default")
      (node (ref "C78") (pin "1") (pinfunction "1_1") (pintype "passive"))
      (node (ref "IC1") (pin "38") (pinfunction "P1[24]/MCFB2/PWM1[5]/MOSI0_38") (pintype "bidirectional"))
      (node (ref "R92") (pin "2") (pinfunction "2_2") (pintype "passive"))
    )
    (net (code "79") (name "/Y_MAX") (class "Default")
      (node (ref "C81") (pin "1") (pinfunction "1_1") (pintype "passive"))
      (node (ref "IC1") (pin "43") (pinfunction "P1[27]/CLKOUT/USB_OVRCR/CAP0[1]_43") (pintype "bidirectional"))
      (node (ref "R99") (pin "2") (pinfunction "2_2") (pintype "passive"))
    )
    (net (code "80") (name "/Y_MIN") (class "Default")
      (node (ref "C80") (pin "1") (pinfunction "1_1") (pintype "passive"))
      (node (ref "IC1") (pin "40") (pinfunction "P1[26]/MC1B/PWM1[6]/CAP0[0]_40") (pintype "bidirectional"))
      (node (ref "R97") (pin "2") (pinfunction "2_2") (pintype "passive"))
    )
    (net (code "81") (name "/Z_MAX") (class "Default")
      (node (ref "C83") (pin "1") (pinfunction "1_1") (pintype "passive"))
      (node (ref "IC1") (pin "45") (pinfunction "P1[29]/MC2B/PCAP1[1]/MAT0[1]_45") (pintype "bidirectional"))
      (node (ref "R103") (pin "2") (pinfunction "2_2") (pintype "passive"))
    )
    (net (code "82") (name "/Z_MIN") (class "Default")
      (node (ref "C82") (pin "1") (pinfunction "1_1") (pintype "passive"))
      (node (ref "IC1") (pin "44") (pinfunction "P1[28]/MC2A/PCAP1[0]/MAT0[0]_44") (pintype "bidirectional"))
      (node (ref "R101") (pin "2") (pinfunction "2_2") (pintype "passive"))
    )
    (net (code "83") (name "3.3V") (class "Default")
      (node (ref "C1") (pin "2") (pinfunction "2_2") (pintype "passive"))
      (node (ref "C10") (pin "2") (pinfunction "2_2") (pintype "passive"))
      (node (ref "C11") (pin "2") (pinfunction "2_2") (pintype "passive"))
      (node (ref "C12") (pin "2") (pinfunction "2_2") (pintype "passive"))
      (node (ref "C13") (pin "2") (pinfunction "2_2") (pintype "passive"))
      (node (ref "C14") (pin "2") (pinfunction "2_2") (pintype "passive"))
      (node (ref "C67") (pin "2") (pinfunction "2_2") (pintype "passive"))
      (node (ref "C7") (pin "A") (pinfunction "+_A") (pintype "passive"))
      (node (ref "C8") (pin "2") (pinfunction "2_2") (pintype "passive"))
      (node (ref "C9") (pin "2") (pinfunction "2_2") (pintype "passive"))
      (node (ref "IC1") (pin "19") (pinfunction "VBAT_19") (pintype "bidirectional"))
      (node (ref "IC1") (pin "28") (pinfunction "VDD(3V3)1_28") (pintype "bidirectional"))
      (node (ref "IC1") (pin "42") (pinfunction "VDD(REG)(3V3)1_42") (pintype "bidirectional"))
      (node (ref "IC1") (pin "54") (pinfunction "VDD(3V3)2_54") (pintype "bidirectional"))
      (node (ref "IC1") (pin "71") (pinfunction "VDD(3V3)3_71") (pintype "bidirectional"))
      (node (ref "IC1") (pin "84") (pinfunction "VDD(REG)(3V3)2_84") (pintype "bidirectional"))
      (node (ref "IC1") (pin "96") (pinfunction "VDD(3V3)4_96") (pintype "bidirectional"))
      (node (ref "JP1") (pin "1") (pinfunction "1_1") (pintype "passive"))
      (node (ref "JP17") (pin "2") (pinfunction "2_2") (pintype "passive"))
      (node (ref "JP2") (pin "1") (pinfunction "1_1") (pintype "passive"))
      (node (ref "JP4") (pin "1") (pinfunction "1_1") (pintype "passive"))
      (node (ref "L1") (pin "2") (pinfunction "2_2") (pintype "passive"))
      (node (ref "Q1") (pin "4") (pinfunction "S_4") (pintype "passive"))
      (node (ref "R1") (pin "2") (pinfunction "2_2") (pintype "passive"))
      (node (ref "R14") (pin "2") (pinfunction "2_2") (pintype "passive"))
      (node (ref "R15") (pin "2") (pinfunction "2_2") (pintype "passive"))
      (node (ref "R16") (pin "2") (pinfunction "2_2") (pintype "passive"))
      (node (ref "R17") (pin "1") (pinfunction "1_1") (pintype "passive"))
      (node (ref "R2") (pin "2") (pinfunction "2_2") (pintype "passive"))
      (node (ref "R3") (pin "2") (pinfunction "2_2") (pintype "passive"))
      (node (ref "SJ1") (pin "1") (pinfunction "1_1") (pintype "passive"))
      (node (ref "SJ2") (pin "1") (pinfunction "1_1") (pintype "passive"))
      (node (ref "SJ3") (pin "1") (pinfunction "1_1") (pintype "passive"))
      (node (ref "U1") (pin "4") (pinfunction "VCC_4") (pintype "bidirectional"))
    )
    (net (code "84") (name "5V") (class "Default")
      (node (ref "SJ1") (pin "3") (pinfunction "3_3") (pintype "passive"))
      (node (ref "SJ2") (pin "3") (pinfunction "3_3") (pintype "passive"))
      (node (ref "SJ3") (pin "3") (pinfunction "3_3") (pintype "passive"))
    )
    (net (code "85") (name "AGND") (class "Default")
      (node (ref "C1") (pin "1") (pinfunction "1_1") (pintype "passive"))
      (node (ref "C10") (pin "1") (pinfunction "1_1") (pintype "passive"))
      (node (ref "C11") (pin "1") (pinfunction "1_1") (pintype "passive"))
      (node (ref "C12") (pin "1") (pinfunction "1_1") (pintype "passive"))
      (node (ref "C13") (pin "1") (pinfunction "1_1") (pintype "passive"))
      (node (ref "C14") (pin "1") (pinfunction "1_1") (pintype "passive"))
      (node (ref "C2") (pin "2") (pinfunction "2_2") (pintype "passive"))
      (node (ref "C3") (pin "2") (pinfunction "2_2") (pintype "passive"))
      (node (ref "C4") (pin "1") (pinfunction "1_1") (pintype "passive"))
      (node (ref "C5") (pin "1") (pinfunction "1_1") (pintype "passive"))
      (node (ref "C6") (pin "2") (pinfunction "2_2") (pintype "passive"))
      (node (ref "C67") (pin "1") (pinfunction "1_1") (pintype "passive"))
      (node (ref "C7") (pin "C") (pinfunction "-_C") (pintype "passive"))
      (node (ref "C78") (pin "2") (pinfunction "2_2") (pintype "passive"))
      (node (ref "C79") (pin "2") (pinfunction "2_2") (pintype "passive"))
      (node (ref "C8") (pin "1") (pinfunction "1_1") (pintype "passive"))
      (node (ref "C80") (pin "2") (pinfunction "2_2") (pintype "passive"))
      (node (ref "C81") (pin "2") (pinfunction "2_2") (pintype "passive"))
      (node (ref "C82") (pin "2") (pinfunction "2_2") (pintype "passive"))
      (node (ref "C83") (pin "2") (pinfunction "2_2") (pintype "passive"))
      (node (ref "C9") (pin "1") (pinfunction "1_1") (pintype "passive"))
      (node (ref "IC1") (pin "11") (pinfunction "VSSA_11") (pintype "bidirectional"))
      (node (ref "IC1") (pin "15") (pinfunction "VREFN_15") (pintype "bidirectional"))
      (node (ref "IC1") (pin "31") (pinfunction "VSS1_31") (pintype "bidirectional"))
      (node (ref "IC1") (pin "41") (pinfunction "VSS2_41") (pintype "bidirectional"))
      (node (ref "IC1") (pin "55") (pinfunction "VSS3_55") (pintype "bidirectional"))
      (node (ref "IC1") (pin "72") (pinfunction "VSS4_72") (pintype "bidirectional"))
      (node (ref "IC1") (pin "83") (pinfunction "VSS6_83") (pintype "bidirectional"))
      (node (ref "IC1") (pin "97") (pinfunction "VSS5_97") (pintype "bidirectional"))
      (node (ref "JP1") (pin "2") (pinfunction "2_2") (pintype "passive"))
      (node (ref "JP10") (pin "1") (pinfunction "1_1") (pintype "passive"))
      (node (ref "JP10") (pin "2") (pinfunction "2_2") (pintype "passive"))
      (node (ref "JP10") (pin "3") (pinfunction "3_3") (pintype "passive"))
      (node (ref "JP10") (pin "4") (pinfunction "4_4") (pintype "passive"))
      (node (ref "JP12") (pin "4") (pinfunction "4_4") (pintype "passive"))
      (node (ref "JP14") (pin "2") (pinfunction "2_2") (pintype "passive"))
      (node (ref "JP15") (pin "4") (pinfunction "4_4") (pintype "passive"))
      (node (ref "JP16") (pin "2") (pinfunction "2_2") (pintype "passive"))
      (node (ref "JP17") (pin "3") (pinfunction "3_3") (pintype "passive"))
      (node (ref "JP19") (pin "2") (pinfunction "2_2") (pintype "passive"))
      (node (ref "JP21") (pin "2") (pinfunction "2_2") (pintype "passive"))
      (node (ref "JP22") (pin "2") (pinfunction "2_2") (pintype "passive"))
      (node (ref "JP23") (pin "2") (pinfunction "2_2") (pintype "passive"))
      (node (ref "JP25") (pin "2") (pinfunction "2_2") (pintype "passive"))
      (node (ref "JP26") (pin "2") (pinfunction "2_2") (pintype "passive"))
      (node (ref "JP3") (pin "3") (pinfunction "3_3") (pintype "passive"))
      (node (ref "JP32") (pin "5") (pinfunction "5_5") (pintype "passive"))
      (node (ref "JP33") (pin "5") (pinfunction "5_5") (pintype "passive"))
      (node (ref "JP5") (pin "1") (pinfunction "1_1") (pintype "passive"))
      (node (ref "JP6") (pin "3") (pinfunction "3_3") (pintype "passive"))
      (node (ref "JP7") (pin "4") (pinfunction "4_4") (pintype "passive"))
      (node (ref "JP9") (pin "4") (pinfunction "4_4") (pintype "passive"))
      (node (ref "LED1") (pin "C") (pinfunction "C_C") (pintype "passive"))
      (node (ref "LED2") (pin "C") (pinfunction "C_C") (pintype "passive"))
      (node (ref "LED3") (pin "C") (pinfunction "C_C") (pintype "passive"))
      (node (ref "LED4") (pin "C") (pinfunction "C_C") (pintype "passive"))
      (node (ref "S1") (pin "3") (pinfunction "3_3") (pintype "passive"))
      (node (ref "S1") (pin "4") (pinfunction "4_4") (pintype "passive"))
      (node (ref "S2") (pin "3") (pinfunction "3_3") (pintype "passive"))
      (node (ref "S2") (pin "4") (pinfunction "4_4") (pintype "passive"))
      (node (ref "S3") (pin "2") (pinfunction "2_2") (pintype "passive"))
      (node (ref "U1") (pin "6") (pinfunction "GND_6") (pintype "bidirectional"))
      (node (ref "U1") (pin "CD2") (pinfunction "SHIELD_CD2") (pintype "bidirectional"))
      (node (ref "U1") (pin "GND1") (pinfunction "SHIELD_GND1") (pintype "bidirectional"))
      (node (ref "X14") (pin "GND") (pinfunction "GND_GND") (pintype "bidirectional"))
    )
    (net (code "86") (name "Net-(IC1-XTAL1)") (class "Default")
      (node (ref "C2") (pin "1") (pinfunction "1_1") (pintype "passive"))
      (node (ref "IC1") (pin "22") (pinfunction "XTAL1_22") (pintype "bidirectional"))
      (node (ref "Q2") (pin "2") (pinfunction "2_2") (pintype "passive"))
    )
    (net (code "87") (name "Net-(IC1-XTAL2)") (class "Default")
      (node (ref "C3") (pin "1") (pinfunction "1_1") (pintype "passive"))
      (node (ref "IC1") (pin "23") (pinfunction "XTAL2_23") (pintype "bidirectional"))
      (node (ref "Q2") (pin "1") (pinfunction "1_1") (pintype "passive"))
    )
    (net (code "88") (name "Net-(JP5-Pad3)") (class "Default")
      (node (ref "JP5") (pin "3") (pinfunction "3_3") (pintype "passive"))
      (node (ref "SJ1") (pin "2") (pinfunction "2_2") (pintype "passive"))
    )
    (net (code "89") (name "Net-(JP14-Pad1)") (class "Default")
      (node (ref "JP14") (pin "1") (pinfunction "1_1") (pintype "passive"))
      (node (ref "JP16") (pin "1") (pinfunction "1_1") (pintype "passive"))
      (node (ref "JP19") (pin "1") (pinfunction "1_1") (pintype "passive"))
      (node (ref "JP21") (pin "1") (pinfunction "1_1") (pintype "passive"))
      (node (ref "JP22") (pin "1") (pinfunction "1_1") (pintype "passive"))
      (node (ref "JP26") (pin "1") (pinfunction "1_1") (pintype "passive"))
      (node (ref "R100") (pin "2") (pinfunction "2_2") (pintype "passive"))
      (node (ref "R102") (pin "2") (pinfunction "2_2") (pintype "passive"))
      (node (ref "R93") (pin "2") (pinfunction "2_2") (pintype "passive"))
      (node (ref "R94") (pin "2") (pinfunction "2_2") (pintype "passive"))
      (node (ref "R96") (pin "2") (pinfunction "2_2") (pintype "passive"))
      (node (ref "R98") (pin "2") (pinfunction "2_2") (pintype "passive"))
      (node (ref "SJ2") (pin "2") (pinfunction "2_2") (pintype "passive"))
    )
    (net (code "90") (name "Net-(JP14-Pad3)") (class "Default")
      (node (ref "JP14") (pin "3") (pinfunction "3_3") (pintype "passive"))
      (node (ref "R94") (pin "1") (pinfunction "1_1") (pintype "passive"))
      (node (ref "R95") (pin "1") (pinfunction "1_1") (pintype "passive"))
    )
    (net (code "91") (name "Net-(JP16-Pad3)") (class "Default")
      (node (ref "JP16") (pin "3") (pinfunction "3_3") (pintype "passive"))
      (node (ref "R96") (pin "1") (pinfunction "1_1") (pintype "passive"))
      (node (ref "R97") (pin "1") (pinfunction "1_1") (pintype "passive"))
    )
    (net (code "92") (name "Net-(JP19-Pad3)") (class "Default")
      (node (ref "JP19") (pin "3") (pinfunction "3_3") (pintype "passive"))
      (node (ref "R98") (pin "1") (pinfunction "1_1") (pintype "passive"))
      (node (ref "R99") (pin "1") (pinfunction "1_1") (pintype "passive"))
    )
    (net (code "93") (name "Net-(JP21-Pad3)") (class "Default")
      (node (ref "JP21") (pin "3") (pinfunction "3_3") (pintype "passive"))
      (node (ref "R100") (pin "1") (pinfunction "1_1") (pintype "passive"))
      (node (ref "R101") (pin "1") (pinfunction "1_1") (pintype "passive"))
    )
    (net (code "94") (name "Net-(JP22-Pad3)") (class "Default")
      (node (ref "JP22") (pin "3") (pinfunction "3_3") (pintype "passive"))
      (node (ref "R102") (pin "1") (pinfunction "1_1") (pintype "passive"))
      (node (ref "R103") (pin "1") (pinfunction "1_1") (pintype "passive"))
    )
    (net (code "95") (name "Net-(JP24-Pad1)") (class "Default")
      (node (ref "JP24") (pin "1") (pinfunction "1_1") (pintype "passive"))
      (node (ref "R17") (pin "2") (pinfunction "2_2") (pintype "passive"))
      (node (ref "S3") (pin "C") (pinfunction "C_C") (pintype "passive"))
    )
    (net (code "96") (name "Net-(JP26-Pad3)") (class "Default")
      (node (ref "JP26") (pin "3") (pinfunction "3_3") (pintype "passive"))
      (node (ref "R92") (pin "1") (pinfunction "1_1") (pintype "passive"))
      (node (ref "R93") (pin "1") (pinfunction "1_1") (pintype "passive"))
    )
    (net (code "97") (name "Net-(LED1-PadA)") (class "Default")
      (node (ref "LED1") (pin "A") (pinfunction "A_A") (pintype "passive"))
      (node (ref "R10") (pin "1") (pinfunction "1_1") (pintype "passive"))
    )
    (net (code "98") (name "Net-(LED2-PadA)") (class "Default")
      (node (ref "LED2") (pin "A") (pinfunction "A_A") (pintype "passive"))
      (node (ref "R11") (pin "1") (pinfunction "1_1") (pintype "passive"))
    )
    (net (code "99") (name "Net-(LED3-PadA)") (class "Default")
      (node (ref "LED3") (pin "A") (pinfunction "A_A") (pintype "passive"))
      (node (ref "R12") (pin "1") (pinfunction "1_1") (pintype "passive"))
    )
    (net (code "100") (name "Net-(LED4-PadA)") (class "Default")
      (node (ref "LED4") (pin "A") (pinfunction "A_A") (pintype "passive"))
      (node (ref "R13") (pin "1") (pinfunction "1_1") (pintype "passive"))
    )
    (net (code "101") (name "Net-(Q1-D)") (class "Default")
      (node (ref "Q1") (pin "1_2_5_6") (pinfunction "D_1_2_5_6") (pintype "passive"))
      (node (ref "R7") (pin "2") (pinfunction "2_2") (pintype "passive"))
    )
    (net (code "102") (name "Net-(R5-Pad2)") (class "Default")
      (node (ref "R5") (pin "2") (pinfunction "2_2") (pintype "passive"))
      (node (ref "R6") (pin "2") (pinfunction "2_2") (pintype "passive"))
      (node (ref "SJ3") (pin "2") (pinfunction "2_2") (pintype "passive"))
    )
    (net (code "103") (name "Net-(R8-Pad1)") (class "Default")
      (node (ref "R8") (pin "1") (pinfunction "1_1") (pintype "passive"))
      (node (ref "X14") (pin "D+") (pinfunction "D+_D+") (pintype "bidirectional"))
    )
    (net (code "104") (name "Net-(R9-Pad1)") (class "Default")
      (node (ref "R9") (pin "1") (pinfunction "1_1") (pintype "passive"))
      (node (ref "X14") (pin "D-") (pinfunction "D-_D-") (pintype "bidirectional"))
    )
    (net (code "105") (name "VUSB") (class "Default")
      (node (ref "X14") (pin "VBUS") (pinfunction "VBUS_VBUS") (pintype "bidirectional"))
    )
    (net (code "106") (name "unconnected-(IC1-N.C.-Pad13)") (class "Default")
      (node (ref "IC1") (pin "13") (pinfunction "N.C._13") (pintype "bidirectional"))
    )
    (net (code "107") (name "unconnected-(IC1-RTCX1-Pad16)") (class "Default")
      (node (ref "IC1") (pin "16") (pinfunction "RTCX1_16") (pintype "bidirectional"))
    )
    (net (code "108") (name "unconnected-(IC1-RTCX2-Pad18)") (class "Default")
      (node (ref "IC1") (pin "18") (pinfunction "RTCX2_18") (pintype "bidirectional"))
    )
    (net (code "109") (name "unconnected-(U1-NC-Pad1)") (class "Default")
      (node (ref "U1") (pin "1") (pinfunction "NC_1") (pintype "bidirectional"))
    )
    (net (code "110") (name "unconnected-(U1-RSV-Pad8)") (class "Default")
      (node (ref "U1") (pin "8") (pinfunction "RSV_8") (pintype "bidirectional"))
    )
    (net (code "111") (name "unconnected-(U1-SHIELD-PadCD1)") (class "Default")
      (node (ref "U1") (pin "CD1") (pinfunction "SHIELD_CD1") (pintype "bidirectional"))
    )
    (net (code "112") (name "unconnected-(U1-SHIELD-PadGND3)") (class "Default")
      (node (ref "U1") (pin "GND3") (pinfunction "SHIELD_GND3") (pintype "bidirectional"))
    )
  )
)
